# 04_-_CPU_POWER.net
KiCad netlist of a schematic drawn in Altium Designer
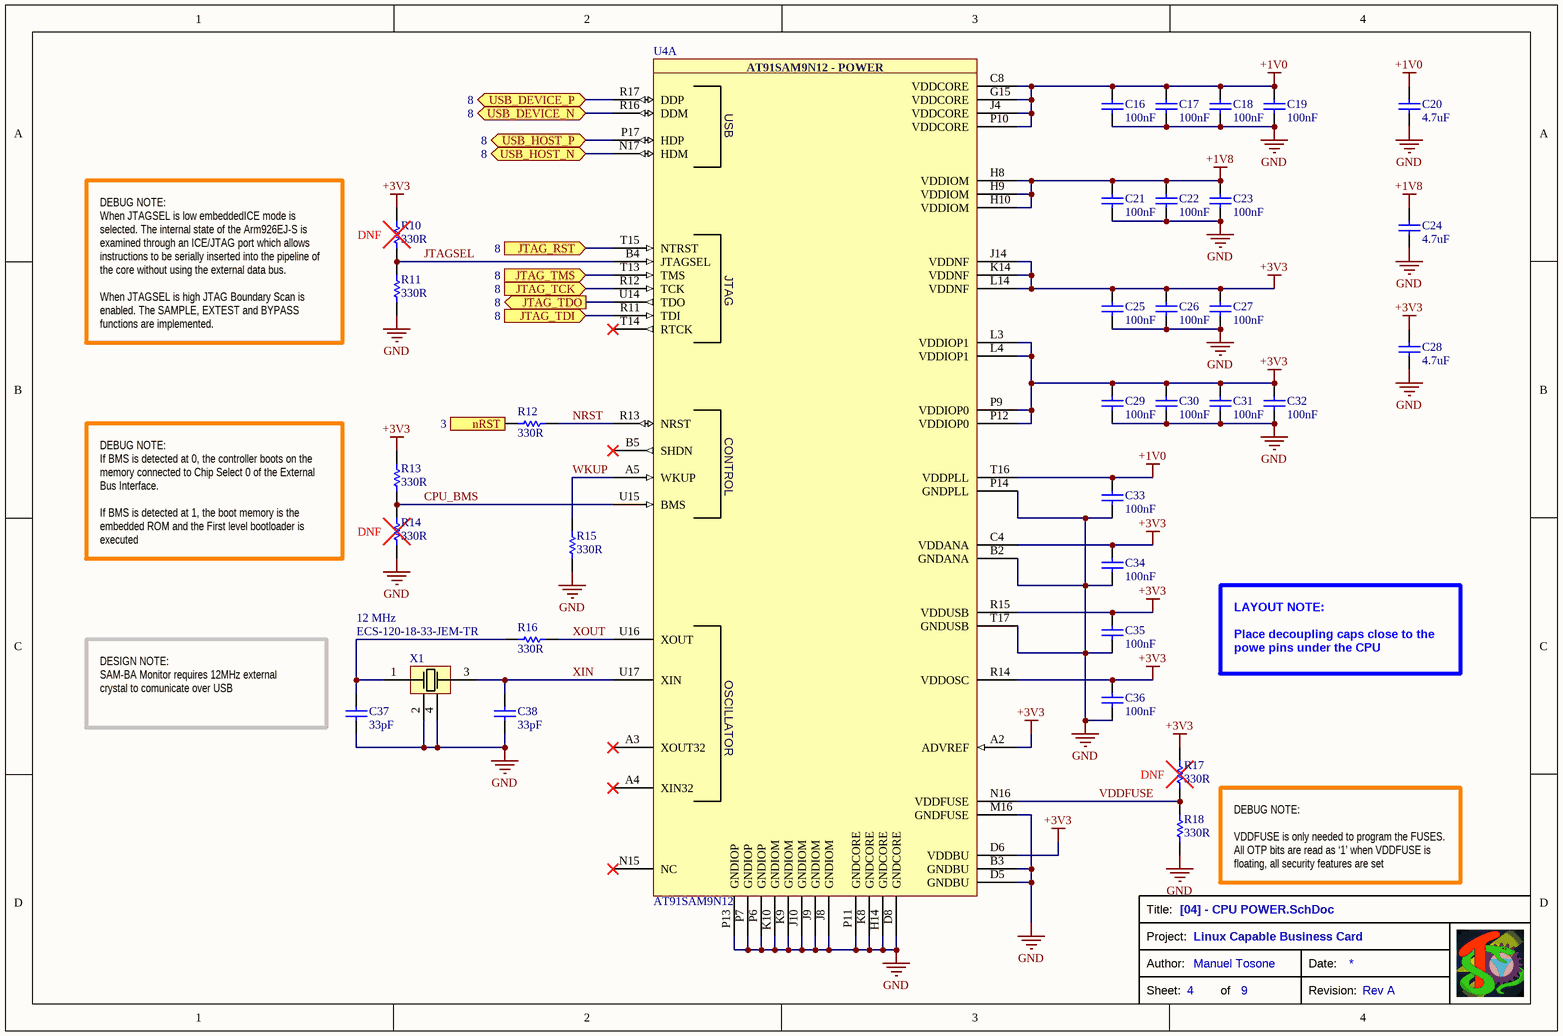
[diagram p0: [04] - CPU POWER.SchDoc]

(export (version "E")
  (design (tool "Eeschema 10.0.6"))
  (components
    (comp (ref "C16")
      (value "100nF")
      (footprint "CAP-0603")
      (description "Multilayer Ceramic Capacitors MLCC - SMD/SMT 16V 0.1uF X7R 0603 20%")
      (fields (field (name "MANUFACTURER") "KEMET") (field (name "Comment") "C0603C104M4RAC"))
      (libsource (lib "Linux-Capable-Business-Card") (part "CAP-0603-100n-C0603C104M4RAC"))
    )
    (comp (ref "C17")
      (value "100nF")
      (footprint "CAP-0603")
      (description "Multilayer Ceramic Capacitors MLCC - SMD/SMT 16V 0.1uF X7R 0603 20%")
      (fields (field (name "MANUFACTURER") "KEMET") (field (name "Comment") "C0603C104M4RAC"))
      (libsource (lib "Linux-Capable-Business-Card") (part "CAP-0603-100n-C0603C104M4RAC"))
    )
    (comp (ref "C18")
      (value "100nF")
      (footprint "CAP-0603")
      (description "Multilayer Ceramic Capacitors MLCC - SMD/SMT 16V 0.1uF X7R 0603 20%")
      (fields (field (name "MANUFACTURER") "KEMET") (field (name "Comment") "C0603C104M4RAC"))
      (libsource (lib "Linux-Capable-Business-Card") (part "CAP-0603-100n-C0603C104M4RAC"))
    )
    (comp (ref "C19")
      (value "100nF")
      (footprint "CAP-0603")
      (description "Multilayer Ceramic Capacitors MLCC - SMD/SMT 16V 0.1uF X7R 0603 20%")
      (fields (field (name "MANUFACTURER") "KEMET") (field (name "Comment") "C0603C104M4RAC"))
      (libsource (lib "Linux-Capable-Business-Card") (part "CAP-0603-100n-C0603C104M4RAC"))
    )
    (comp (ref "C20")
      (value "4.7uF")
      (footprint "CAP-0805")
      (description "Multilayer Ceramic Capacitors MLCC - SMD/SMT WCAP-CSGP 4.7uF 0805 20% 16V MLCC")
      (fields (field (name "MANUFACTURER") "Wurth Elektronik") (field (name "Comment") "885012107013"))
      (libsource (lib "Linux-Capable-Business-Card") (part "CAP-0805-4.7u-885012107013_2"))
    )
    (comp (ref "C21")
      (value "100nF")
      (footprint "CAP-0603")
      (description "Multilayer Ceramic Capacitors MLCC - SMD/SMT 16V 0.1uF X7R 0603 20%")
      (fields (field (name "MANUFACTURER") "KEMET") (field (name "Comment") "C0603C104M4RAC"))
      (libsource (lib "Linux-Capable-Business-Card") (part "CAP-0603-100n-C0603C104M4RAC"))
    )
    (comp (ref "C22")
      (value "100nF")
      (footprint "CAP-0603")
      (description "Multilayer Ceramic Capacitors MLCC - SMD/SMT 16V 0.1uF X7R 0603 20%")
      (fields (field (name "MANUFACTURER") "KEMET") (field (name "Comment") "C0603C104M4RAC"))
      (libsource (lib "Linux-Capable-Business-Card") (part "CAP-0603-100n-C0603C104M4RAC"))
    )
    (comp (ref "C23")
      (value "100nF")
      (footprint "CAP-0603")
      (description "Multilayer Ceramic Capacitors MLCC - SMD/SMT 16V 0.1uF X7R 0603 20%")
      (fields (field (name "MANUFACTURER") "KEMET") (field (name "Comment") "C0603C104M4RAC"))
      (libsource (lib "Linux-Capable-Business-Card") (part "CAP-0603-100n-C0603C104M4RAC"))
    )
    (comp (ref "C24")
      (value "4.7uF")
      (footprint "CAP-0805")
      (description "Multilayer Ceramic Capacitors MLCC - SMD/SMT WCAP-CSGP 4.7uF 0805 20% 16V MLCC")
      (fields (field (name "MANUFACTURER") "Wurth Elektronik") (field (name "Comment") "885012107013"))
      (libsource (lib "Linux-Capable-Business-Card") (part "CAP-0805-4.7u-885012107013_2"))
    )
    (comp (ref "C25")
      (value "100nF")
      (footprint "CAP-0603")
      (description "Multilayer Ceramic Capacitors MLCC - SMD/SMT 16V 0.1uF X7R 0603 20%")
      (fields (field (name "MANUFACTURER") "KEMET") (field (name "Comment") "C0603C104M4RAC"))
      (libsource (lib "Linux-Capable-Business-Card") (part "CAP-0603-100n-C0603C104M4RAC"))
    )
    (comp (ref "C26")
      (value "100nF")
      (footprint "CAP-0603")
      (description "Multilayer Ceramic Capacitors MLCC - SMD/SMT 16V 0.1uF X7R 0603 20%")
      (fields (field (name "MANUFACTURER") "KEMET") (field (name "Comment") "C0603C104M4RAC"))
      (libsource (lib "Linux-Capable-Business-Card") (part "CAP-0603-100n-C0603C104M4RAC"))
    )
    (comp (ref "C27")
      (value "100nF")
      (footprint "CAP-0603")
      (description "Multilayer Ceramic Capacitors MLCC - SMD/SMT 16V 0.1uF X7R 0603 20%")
      (fields (field (name "MANUFACTURER") "KEMET") (field (name "Comment") "C0603C104M4RAC"))
      (libsource (lib "Linux-Capable-Business-Card") (part "CAP-0603-100n-C0603C104M4RAC"))
    )
    (comp (ref "C28")
      (value "4.7uF")
      (footprint "CAP-0805")
      (description "Multilayer Ceramic Capacitors MLCC - SMD/SMT WCAP-CSGP 4.7uF 0805 20% 16V MLCC")
      (fields (field (name "MANUFACTURER") "Wurth Elektronik") (field (name "Comment") "885012107013"))
      (libsource (lib "Linux-Capable-Business-Card") (part "CAP-0805-4.7u-885012107013_2"))
    )
    (comp (ref "C29")
      (value "100nF")
      (footprint "CAP-0603")
      (description "Multilayer Ceramic Capacitors MLCC - SMD/SMT 16V 0.1uF X7R 0603 20%")
      (fields (field (name "MANUFACTURER") "KEMET") (field (name "Comment") "C0603C104M4RAC"))
      (libsource (lib "Linux-Capable-Business-Card") (part "CAP-0603-100n-C0603C104M4RAC"))
    )
    (comp (ref "C30")
      (value "100nF")
      (footprint "CAP-0603")
      (description "Multilayer Ceramic Capacitors MLCC - SMD/SMT 16V 0.1uF X7R 0603 20%")
      (fields (field (name "MANUFACTURER") "KEMET") (field (name "Comment") "C0603C104M4RAC"))
      (libsource (lib "Linux-Capable-Business-Card") (part "CAP-0603-100n-C0603C104M4RAC"))
    )
    (comp (ref "C31")
      (value "100nF")
      (footprint "CAP-0603")
      (description "Multilayer Ceramic Capacitors MLCC - SMD/SMT 16V 0.1uF X7R 0603 20%")
      (fields (field (name "MANUFACTURER") "KEMET") (field (name "Comment") "C0603C104M4RAC"))
      (libsource (lib "Linux-Capable-Business-Card") (part "CAP-0603-100n-C0603C104M4RAC"))
    )
    (comp (ref "C32")
      (value "100nF")
      (footprint "CAP-0603")
      (description "Multilayer Ceramic Capacitors MLCC - SMD/SMT 16V 0.1uF X7R 0603 20%")
      (fields (field (name "MANUFACTURER") "KEMET") (field (name "Comment") "C0603C104M4RAC"))
      (libsource (lib "Linux-Capable-Business-Card") (part "CAP-0603-100n-C0603C104M4RAC"))
    )
    (comp (ref "C33")
      (value "100nF")
      (footprint "CAP-0603")
      (description "Multilayer Ceramic Capacitors MLCC - SMD/SMT 16V 0.1uF X7R 0603 20%")
      (fields (field (name "MANUFACTURER") "KEMET") (field (name "Comment") "C0603C104M4RAC"))
      (libsource (lib "Linux-Capable-Business-Card") (part "CAP-0603-100n-C0603C104M4RAC"))
    )
    (comp (ref "C34")
      (value "100nF")
      (footprint "CAP-0603")
      (description "Multilayer Ceramic Capacitors MLCC - SMD/SMT 16V 0.1uF X7R 0603 20%")
      (fields (field (name "MANUFACTURER") "KEMET") (field (name "Comment") "C0603C104M4RAC"))
      (libsource (lib "Linux-Capable-Business-Card") (part "CAP-0603-100n-C0603C104M4RAC"))
    )
    (comp (ref "C35")
      (value "100nF")
      (footprint "CAP-0603")
      (description "Multilayer Ceramic Capacitors MLCC - SMD/SMT 16V 0.1uF X7R 0603 20%")
      (fields (field (name "MANUFACTURER") "KEMET") (field (name "Comment") "C0603C104M4RAC"))
      (libsource (lib "Linux-Capable-Business-Card") (part "CAP-0603-100n-C0603C104M4RAC"))
    )
    (comp (ref "C36")
      (value "100nF")
      (footprint "CAP-0603")
      (description "Multilayer Ceramic Capacitors MLCC - SMD/SMT 16V 0.1uF X7R 0603 20%")
      (fields (field (name "MANUFACTURER") "KEMET") (field (name "Comment") "C0603C104M4RAC"))
      (libsource (lib "Linux-Capable-Business-Card") (part "CAP-0603-100n-C0603C104M4RAC"))
    )
    (comp (ref "C37")
      (value "33pF")
      (footprint "CAP-0603")
      (description "Multilayer Ceramic Capacitors MLCC - SMD/SMT WCAP-CSGP 33pF 0603 5% 50V MLCC")
      (fields (field (name "MANUFACTURER") "Wurth Elektronik") (field (name "Comment") "885012006054"))
      (libsource (lib "Linux-Capable-Business-Card") (part "CAP-0603-33p-885012006054"))
    )
    (comp (ref "C38")
      (value "33pF")
      (footprint "CAP-0603")
      (description "Multilayer Ceramic Capacitors MLCC - SMD/SMT WCAP-CSGP 33pF 0603 5% 50V MLCC")
      (fields (field (name "MANUFACTURER") "Wurth Elektronik") (field (name "Comment") "885012006054"))
      (libsource (lib "Linux-Capable-Business-Card") (part "CAP-0603-33p-885012006054"))
    )
    (comp (ref "R10")
      (value "330R")
      (footprint "RES-0603")
      (description "Thin Film Resistors - SMD 1/10W 330 ohm 1% 50ppm")
      (fields (field (name "MANUFACTURER") "Yageo") (field (name "Comment") "RT0603FRD07330RL"))
      (libsource (lib "Linux-Capable-Business-Card") (part "RES-0603-330R-RT0603FRD07330RL"))
    )
    (comp (ref "R11")
      (value "330R")
      (footprint "RES-0603")
      (description "Thin Film Resistors - SMD 1/10W 330 ohm 1% 50ppm")
      (fields (field (name "MANUFACTURER") "Yageo") (field (name "Comment") "RT0603FRD07330RL"))
      (libsource (lib "Linux-Capable-Business-Card") (part "RES-0603-330R-RT0603FRD07330RL"))
    )
    (comp (ref "R12")
      (value "330R")
      (footprint "RES-0603")
      (description "Thin Film Resistors - SMD 1/10W 330 ohm 1% 50ppm")
      (fields (field (name "MANUFACTURER") "Yageo") (field (name "Comment") "RT0603FRD07330RL"))
      (libsource (lib "Linux-Capable-Business-Card") (part "RES-0603-330R-RT0603FRD07330RL"))
    )
    (comp (ref "R13")
      (value "330R")
      (footprint "RES-0603")
      (description "Thin Film Resistors - SMD 1/10W 330 ohm 1% 50ppm")
      (fields (field (name "MANUFACTURER") "Yageo") (field (name "Comment") "RT0603FRD07330RL"))
      (libsource (lib "Linux-Capable-Business-Card") (part "RES-0603-330R-RT0603FRD07330RL"))
    )
    (comp (ref "R14")
      (value "330R")
      (footprint "RES-0603")
      (description "Thin Film Resistors - SMD 1/10W 330 ohm 1% 50ppm")
      (fields (field (name "MANUFACTURER") "Yageo") (field (name "Comment") "RT0603FRD07330RL"))
      (libsource (lib "Linux-Capable-Business-Card") (part "RES-0603-330R-RT0603FRD07330RL"))
    )
    (comp (ref "R15")
      (value "330R")
      (footprint "RES-0603")
      (description "Thin Film Resistors - SMD 1/10W 330 ohm 1% 50ppm")
      (fields (field (name "MANUFACTURER") "Yageo") (field (name "Comment") "RT0603FRD07330RL"))
      (libsource (lib "Linux-Capable-Business-Card") (part "RES-0603-330R-RT0603FRD07330RL"))
    )
    (comp (ref "R16")
      (value "330R")
      (footprint "RES-0603")
      (description "Thin Film Resistors - SMD 1/10W 330 ohm 1% 50ppm")
      (fields (field (name "MANUFACTURER") "Yageo") (field (name "Comment") "RT0603FRD07330RL"))
      (libsource (lib "Linux-Capable-Business-Card") (part "RES-0603-330R-RT0603FRD07330RL"))
    )
    (comp (ref "R17")
      (value "330R")
      (footprint "RES-0603")
      (description "Thin Film Resistors - SMD 1/10W 330 ohm 1% 50ppm")
      (fields (field (name "MANUFACTURER") "Yageo") (field (name "Comment") "RT0603FRD07330RL"))
      (libsource (lib "Linux-Capable-Business-Card") (part "RES-0603-330R-RT0603FRD07330RL"))
    )
    (comp (ref "R18")
      (value "330R")
      (footprint "RES-0603")
      (description "Thin Film Resistors - SMD 1/10W 330 ohm 1% 50ppm")
      (fields (field (name "MANUFACTURER") "Yageo") (field (name "Comment") "RT0603FRD07330RL"))
      (libsource (lib "Linux-Capable-Business-Card") (part "RES-0603-330R-RT0603FRD07330RL"))
    )
    (comp (ref "U4")
      (value "AT91SAM9N12")
      (footprint "BGA0.8P17X17_217_15X15")
      (description "MPU ARM926EJ-S 400MHz")
      (libsource (lib "Linux-Capable-Business-Card") (part "AT91SAM9N12"))
    )
    (comp (ref "X1")
      (value "ECS-120-18-33-JEM-TR")
      (footprint "XTAL-ECX32-3.2X2.5")
      (description "Crystals 12MHz 20ppm 18pF -20C +70C")
      (fields (field (name "ALTIUM_VALUE") "12 MHz"))
      (libsource (lib "Linux-Capable-Business-Card") (part "XTAL-12MHz-ECS-120-18-33-JEM-TR"))
    )
  )
  (nets
    (net (code "1") (name "+1V0") (class "Default")
      (node (ref "C16") (pin "2") (pinfunction "2_2") (pintype "passive"))
      (node (ref "C17") (pin "2") (pinfunction "2_2") (pintype "passive"))
      (node (ref "C18") (pin "2") (pinfunction "2_2") (pintype "passive"))
      (node (ref "C19") (pin "2") (pinfunction "2_2") (pintype "passive"))
      (node (ref "C20") (pin "2") (pinfunction "2_2") (pintype "passive"))
      (node (ref "C33") (pin "2") (pinfunction "2_2") (pintype "passive"))
      (node (ref "U4") (pin "C8") (pinfunction "VDDCORE_C8") (pintype "power_in"))
      (node (ref "U4") (pin "G15") (pinfunction "VDDCORE_G15") (pintype "power_in"))
      (node (ref "U4") (pin "J4") (pinfunction "VDDCORE_J4") (pintype "power_in"))
      (node (ref "U4") (pin "P10") (pinfunction "VDDCORE_P10") (pintype "power_in"))
      (node (ref "U4") (pin "T16") (pinfunction "VDDPLL_T16") (pintype "power_in"))
    )
    (net (code "2") (name "+1V8") (class "Default")
      (node (ref "C21") (pin "2") (pinfunction "2_2") (pintype "passive"))
      (node (ref "C22") (pin "2") (pinfunction "2_2") (pintype "passive"))
      (node (ref "C23") (pin "2") (pinfunction "2_2") (pintype "passive"))
      (node (ref "C24") (pin "2") (pinfunction "2_2") (pintype "passive"))
      (node (ref "U4") (pin "H10") (pinfunction "VDDIOM_H10") (pintype "power_in"))
      (node (ref "U4") (pin "H8") (pinfunction "VDDIOM_H8") (pintype "power_in"))
      (node (ref "U4") (pin "H9") (pinfunction "VDDIOM_H9") (pintype "power_in"))
    )
    (net (code "3") (name "+3V3") (class "Default")
      (node (ref "C25") (pin "2") (pinfunction "2_2") (pintype "passive"))
      (node (ref "C26") (pin "2") (pinfunction "2_2") (pintype "passive"))
      (node (ref "C27") (pin "2") (pinfunction "2_2") (pintype "passive"))
      (node (ref "C28") (pin "2") (pinfunction "2_2") (pintype "passive"))
      (node (ref "C29") (pin "2") (pinfunction "2_2") (pintype "passive"))
      (node (ref "C30") (pin "2") (pinfunction "2_2") (pintype "passive"))
      (node (ref "C31") (pin "2") (pinfunction "2_2") (pintype "passive"))
      (node (ref "C32") (pin "2") (pinfunction "2_2") (pintype "passive"))
      (node (ref "C34") (pin "2") (pinfunction "2_2") (pintype "passive"))
      (node (ref "C35") (pin "2") (pinfunction "2_2") (pintype "passive"))
      (node (ref "C36") (pin "2") (pinfunction "2_2") (pintype "passive"))
      (node (ref "R10") (pin "2") (pinfunction "2_2") (pintype "passive"))
      (node (ref "R13") (pin "2") (pinfunction "2_2") (pintype "passive"))
      (node (ref "R17") (pin "2") (pinfunction "2_2") (pintype "passive"))
      (node (ref "U4") (pin "A2") (pinfunction "ADVREF_A2") (pintype "input"))
      (node (ref "U4") (pin "C4") (pinfunction "VDDANA_C4") (pintype "power_in"))
      (node (ref "U4") (pin "D6") (pinfunction "VDDBU_D6") (pintype "power_in"))
      (node (ref "U4") (pin "J14") (pinfunction "VDDNF_J14") (pintype "power_in"))
      (node (ref "U4") (pin "K14") (pinfunction "VDDNF_K14") (pintype "power_in"))
      (node (ref "U4") (pin "L14") (pinfunction "VDDNF_L14") (pintype "power_in"))
      (node (ref "U4") (pin "L3") (pinfunction "VDDIOP1_L3") (pintype "power_in"))
      (node (ref "U4") (pin "L4") (pinfunction "VDDIOP1_L4") (pintype "power_in"))
      (node (ref "U4") (pin "P12") (pinfunction "VDDIOP0_P12") (pintype "power_in"))
      (node (ref "U4") (pin "P9") (pinfunction "VDDIOP0_P9") (pintype "power_in"))
      (node (ref "U4") (pin "R14") (pinfunction "VDDOSC_R14") (pintype "power_in"))
      (node (ref "U4") (pin "R15") (pinfunction "VDDUSB_R15") (pintype "power_in"))
    )
    (net (code "4") (name "/CPU_BMS") (class "Default")
      (node (ref "R13") (pin "1") (pinfunction "1_1") (pintype "passive"))
      (node (ref "R14") (pin "2") (pinfunction "2_2") (pintype "passive"))
      (node (ref "U4") (pin "U15") (pinfunction "BMS_U15") (pintype "input"))
    )
    (net (code "5") (name "/JTAGSEL") (class "Default")
      (node (ref "R10") (pin "1") (pinfunction "1_1") (pintype "passive"))
      (node (ref "R11") (pin "2") (pinfunction "2_2") (pintype "passive"))
      (node (ref "U4") (pin "B4") (pinfunction "JTAGSEL_B4") (pintype "input"))
    )
    (net (code "6") (name "/JTAG_RST") (class "Default")
      (node (ref "U4") (pin "T15") (pinfunction "NTRST_T15") (pintype "input"))
    )
    (net (code "7") (name "/JTAG_TCK") (class "Default")
      (node (ref "U4") (pin "R12") (pinfunction "TCK_R12") (pintype "input"))
    )
    (net (code "8") (name "/JTAG_TDI") (class "Default")
      (node (ref "U4") (pin "R11") (pinfunction "TDI_R11") (pintype "input"))
    )
    (net (code "9") (name "/JTAG_TDO") (class "Default")
      (node (ref "U4") (pin "U14") (pinfunction "TDO_U14") (pintype "output"))
    )
    (net (code "10") (name "/JTAG_TMS") (class "Default")
      (node (ref "U4") (pin "T13") (pinfunction "TMS_T13") (pintype "input"))
    )
    (net (code "11") (name "/NRST") (class "Default")
      (node (ref "R12") (pin "2") (pinfunction "2_2") (pintype "passive"))
      (node (ref "U4") (pin "R13") (pinfunction "NRST_R13") (pintype "bidirectional"))
    )
    (net (code "12") (name "/USB_DEVICE_N") (class "Default")
      (node (ref "U4") (pin "R16") (pinfunction "DDM_R16") (pintype "bidirectional"))
    )
    (net (code "13") (name "/USB_DEVICE_P") (class "Default")
      (node (ref "U4") (pin "R17") (pinfunction "DDP_R17") (pintype "bidirectional"))
    )
    (net (code "14") (name "/USB_HOST_N") (class "Default")
      (node (ref "U4") (pin "N17") (pinfunction "HDM_N17") (pintype "bidirectional"))
    )
    (net (code "15") (name "/USB_HOST_P") (class "Default")
      (node (ref "U4") (pin "P17") (pinfunction "HDP_P17") (pintype "bidirectional"))
    )
    (net (code "16") (name "/VDDFUSE") (class "Default")
      (node (ref "R17") (pin "1") (pinfunction "1_1") (pintype "passive"))
      (node (ref "R18") (pin "2") (pinfunction "2_2") (pintype "passive"))
      (node (ref "U4") (pin "N16") (pinfunction "VDDFUSE_N16") (pintype "power_in"))
    )
    (net (code "17") (name "/WKUP") (class "Default")
      (node (ref "R15") (pin "2") (pinfunction "2_2") (pintype "passive"))
      (node (ref "U4") (pin "A5") (pinfunction "WKUP_A5") (pintype "input"))
    )
    (net (code "18") (name "/XIN") (class "Default")
      (node (ref "C38") (pin "2") (pinfunction "2_2") (pintype "passive"))
      (node (ref "U4") (pin "U17") (pinfunction "XIN_U17") (pintype "passive"))
      (node (ref "X1") (pin "3") (pinfunction "3_3") (pintype "passive"))
    )
    (net (code "19") (name "/XOUT") (class "Default")
      (node (ref "R16") (pin "2") (pinfunction "2_2") (pintype "passive"))
      (node (ref "U4") (pin "U16") (pinfunction "XOUT_U16") (pintype "passive"))
    )
    (net (code "20") (name "/nRST") (class "Default")
      (node (ref "R12") (pin "1") (pinfunction "1_1") (pintype "passive"))
    )
    (net (code "21") (name "GND") (class "Default")
      (node (ref "C16") (pin "1") (pinfunction "1_1") (pintype "passive"))
      (node (ref "C17") (pin "1") (pinfunction "1_1") (pintype "passive"))
      (node (ref "C18") (pin "1") (pinfunction "1_1") (pintype "passive"))
      (node (ref "C19") (pin "1") (pinfunction "1_1") (pintype "passive"))
      (node (ref "C20") (pin "1") (pinfunction "1_1") (pintype "passive"))
      (node (ref "C21") (pin "1") (pinfunction "1_1") (pintype "passive"))
      (node (ref "C22") (pin "1") (pinfunction "1_1") (pintype "passive"))
      (node (ref "C23") (pin "1") (pinfunction "1_1") (pintype "passive"))
      (node (ref "C24") (pin "1") (pinfunction "1_1") (pintype "passive"))
      (node (ref "C25") (pin "1") (pinfunction "1_1") (pintype "passive"))
      (node (ref "C26") (pin "1") (pinfunction "1_1") (pintype "passive"))
      (node (ref "C27") (pin "1") (pinfunction "1_1") (pintype "passive"))
      (node (ref "C28") (pin "1") (pinfunction "1_1") (pintype "passive"))
      (node (ref "C29") (pin "1") (pinfunction "1_1") (pintype "passive"))
      (node (ref "C30") (pin "1") (pinfunction "1_1") (pintype "passive"))
      (node (ref "C31") (pin "1") (pinfunction "1_1") (pintype "passive"))
      (node (ref "C32") (pin "1") (pinfunction "1_1") (pintype "passive"))
      (node (ref "C33") (pin "1") (pinfunction "1_1") (pintype "passive"))
      (node (ref "C34") (pin "1") (pinfunction "1_1") (pintype "passive"))
      (node (ref "C35") (pin "1") (pinfunction "1_1") (pintype "passive"))
      (node (ref "C36") (pin "1") (pinfunction "1_1") (pintype "passive"))
      (node (ref "C37") (pin "1") (pinfunction "1_1") (pintype "passive"))
      (node (ref "C38") (pin "1") (pinfunction "1_1") (pintype "passive"))
      (node (ref "R11") (pin "1") (pinfunction "1_1") (pintype "passive"))
      (node (ref "R14") (pin "1") (pinfunction "1_1") (pintype "passive"))
      (node (ref "R15") (pin "1") (pinfunction "1_1") (pintype "passive"))
      (node (ref "R18") (pin "1") (pinfunction "1_1") (pintype "passive"))
      (node (ref "U4") (pin "B2") (pinfunction "GNDANA_B2") (pintype "power_in"))
      (node (ref "U4") (pin "B3") (pinfunction "GNDBU_B3") (pintype "power_in"))
      (node (ref "U4") (pin "D5") (pinfunction "GNDBU_D5") (pintype "power_in"))
      (node (ref "U4") (pin "D8") (pinfunction "GNDCORE_D8") (pintype "power_in"))
      (node (ref "U4") (pin "H14") (pinfunction "GNDCORE_H14") (pintype "power_in"))
      (node (ref "U4") (pin "J10") (pinfunction "GNDIOM_J10") (pintype "power_in"))
      (node (ref "U4") (pin "J8") (pinfunction "GNDIOM_J8") (pintype "power_in"))
      (node (ref "U4") (pin "J9") (pinfunction "GNDIOM_J9") (pintype "power_in"))
      (node (ref "U4") (pin "K10") (pinfunction "GNDIOM_K10") (pintype "power_in"))
      (node (ref "U4") (pin "K8") (pinfunction "GNDCORE_K8") (pintype "power_in"))
      (node (ref "U4") (pin "K9") (pinfunction "GNDIOM_K9") (pintype "power_in"))
      (node (ref "U4") (pin "M16") (pinfunction "GNDFUSE_M16") (pintype "power_in"))
      (node (ref "U4") (pin "P11") (pinfunction "GNDCORE_P11") (pintype "power_in"))
      (node (ref "U4") (pin "P13") (pinfunction "GNDIOP_P13") (pintype "power_in"))
      (node (ref "U4") (pin "P14") (pinfunction "GNDPLL_P14") (pintype "power_in"))
      (node (ref "U4") (pin "P6") (pinfunction "GNDIOP_P6") (pintype "power_in"))
      (node (ref "U4") (pin "P7") (pinfunction "GNDIOP_P7") (pintype "power_in"))
      (node (ref "U4") (pin "T17") (pinfunction "GNDUSB_T17") (pintype "power_in"))
      (node (ref "X1") (pin "2") (pinfunction "2_2") (pintype "passive"))
      (node (ref "X1") (pin "4") (pinfunction "4_4") (pintype "passive"))
    )
    (net (code "22") (name "Net-(C37-Pad2)") (class "Default")
      (node (ref "C37") (pin "2") (pinfunction "2_2") (pintype "passive"))
      (node (ref "R16") (pin "1") (pinfunction "1_1") (pintype "passive"))
      (node (ref "X1") (pin "1") (pinfunction "1_1") (pintype "passive"))
    )
    (net (code "23") (name "unconnected-(U4A-NC-PadN15)") (class "Default")
      (node (ref "U4") (pin "N15") (pinfunction "NC_N15") (pintype "passive+no_connect"))
    )
    (net (code "24") (name "unconnected-(U4A-RTCK-PadT14)") (class "Default")
      (node (ref "U4") (pin "T14") (pinfunction "RTCK_T14") (pintype "output+no_connect"))
    )
    (net (code "25") (name "unconnected-(U4A-SHDN-PadB5)") (class "Default")
      (node (ref "U4") (pin "B5") (pinfunction "SHDN_B5") (pintype "output+no_connect"))
    )
    (net (code "26") (name "unconnected-(U4A-XIN32-PadA4)") (class "Default")
      (node (ref "U4") (pin "A4") (pinfunction "XIN32_A4") (pintype "passive+no_connect"))
    )
    (net (code "27") (name "unconnected-(U4A-XOUT32-PadA3)") (class "Default")
      (node (ref "U4") (pin "A3") (pinfunction "XOUT32_A3") (pintype "passive+no_connect"))
    )
  )
)
